# SilentStepStick-TMC2100_v13_5V.net
KiCad netlist of a schematic drawn in EAGLE
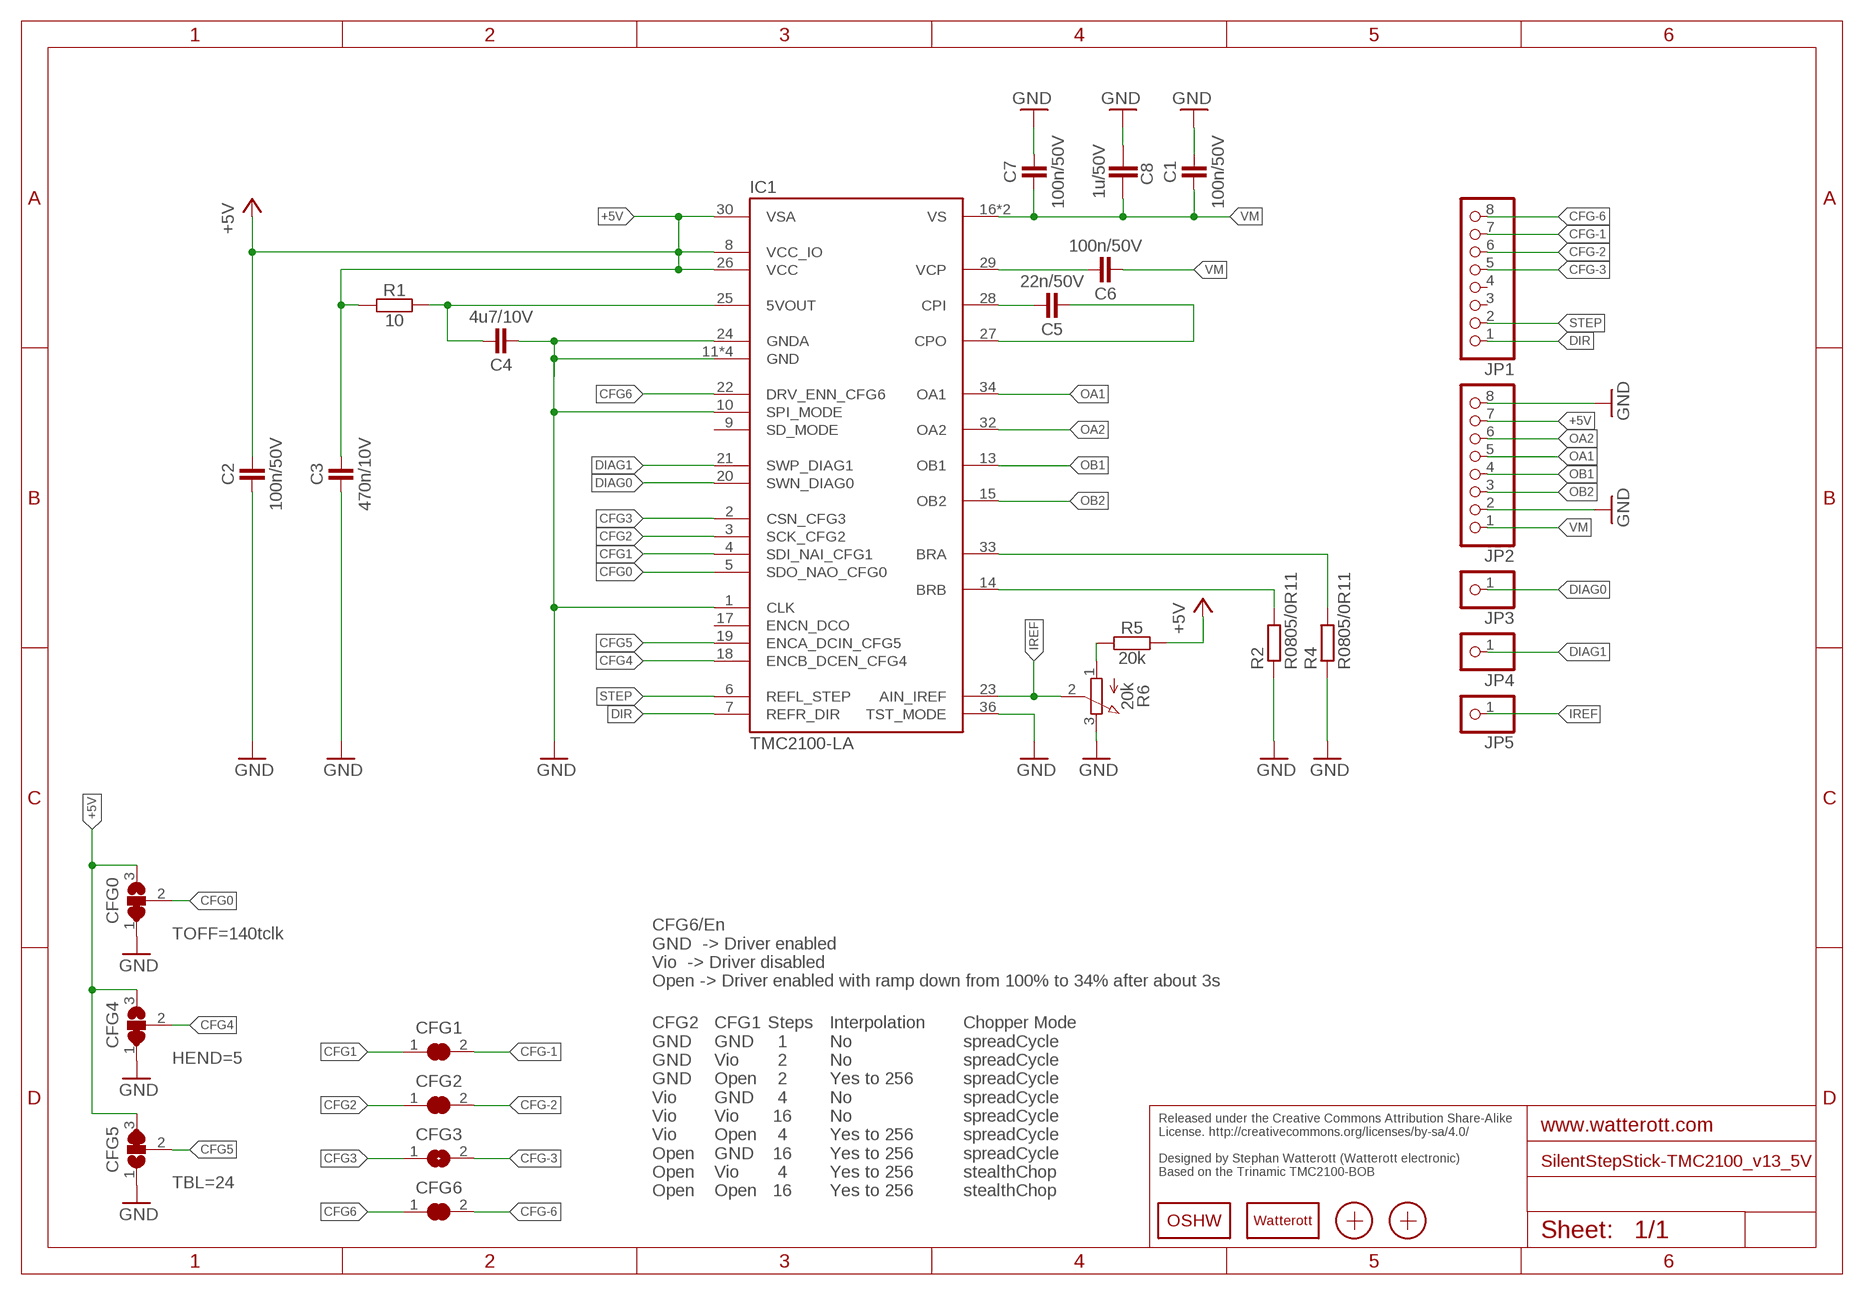
[diagram p0: schematic, sheet 1]

(export (version "E")
  (design (tool "Eeschema 10.0.6"))
  (components
    (comp (ref "C1")
      (value "100n/50V")
      (footprint "eagle-import:C0402")
      (libsource (lib "eagle-import") (part "CAPACITOR-0402"))
    )
    (comp (ref "C2")
      (value "100n/50V")
      (footprint "eagle-import:C0402")
      (libsource (lib "eagle-import") (part "CAPACITOR-0402"))
    )
    (comp (ref "C3")
      (value "470n/10V")
      (footprint "eagle-import:C0402")
      (libsource (lib "eagle-import") (part "CAPACITOR-0402"))
    )
    (comp (ref "C4")
      (value "4u7/10V")
      (footprint "eagle-import:C0402")
      (libsource (lib "eagle-import") (part "CAPACITOR-0402"))
    )
    (comp (ref "C5")
      (value "22n/50V")
      (footprint "eagle-import:C0402")
      (libsource (lib "eagle-import") (part "CAPACITOR-0402"))
    )
    (comp (ref "C6")
      (value "100n/50V")
      (footprint "eagle-import:C0402")
      (libsource (lib "eagle-import") (part "CAPACITOR-0402"))
    )
    (comp (ref "C7")
      (value "100n/50V")
      (footprint "eagle-import:C0402")
      (libsource (lib "eagle-import") (part "CAPACITOR-0402"))
    )
    (comp (ref "C8")
      (value "1u/50V")
      (footprint "eagle-import:C0603")
      (libsource (lib "eagle-import") (part "C-EUC0603"))
    )
    (comp (ref "CFG0")
      (value "JUMPER3-0201")
      (footprint "eagle-import:JUMPER3-0201")
      (libsource (lib "eagle-import") (part "JUMPER3-0201"))
    )
    (comp (ref "CFG1")
      (value "JUMPER2-0201")
      (footprint "eagle-import:JUMPER2-0201")
      (libsource (lib "eagle-import") (part "JUMPER2-0201"))
    )
    (comp (ref "CFG2")
      (value "JUMPER2-0201")
      (footprint "eagle-import:JUMPER2-0201")
      (libsource (lib "eagle-import") (part "JUMPER2-0201"))
    )
    (comp (ref "CFG3")
      (value "JUMPER2-0201")
      (footprint "eagle-import:JUMPER2-0201")
      (libsource (lib "eagle-import") (part "JUMPER2-0201"))
    )
    (comp (ref "CFG4")
      (value "JUMPER3-0201")
      (footprint "eagle-import:JUMPER3-0201")
      (libsource (lib "eagle-import") (part "JUMPER3-0201"))
    )
    (comp (ref "CFG5")
      (value "JUMPER3-0201")
      (footprint "eagle-import:JUMPER3-0201")
      (libsource (lib "eagle-import") (part "JUMPER3-0201"))
    )
    (comp (ref "CFG6")
      (value "JUMPER2-0201")
      (footprint "eagle-import:JUMPER2-0201")
      (libsource (lib "eagle-import") (part "JUMPER2-0201"))
    )
    (comp (ref "IC1")
      (value "TMC2100-LA")
      (footprint "eagle-import:QFN36-PAD")
      (libsource (lib "eagle-import") (part "TMC21X0-LA"))
    )
    (comp (ref "JP1")
      (value "PINHD-1X08_2.54-S")
      (footprint "eagle-import:1X08-S")
      (libsource (lib "eagle-import") (part "PINHD-1X08_2.54-S"))
    )
    (comp (ref "JP2")
      (value "PINHD-1X08_2.54-S")
      (footprint "eagle-import:1X08-S")
      (libsource (lib "eagle-import") (part "PINHD-1X08_2.54-S"))
    )
    (comp (ref "JP3")
      (value "PINHD-1X1")
      (footprint "eagle-import:1X01")
      (libsource (lib "eagle-import") (part "PINHD-1X1"))
    )
    (comp (ref "JP4")
      (value "PINHD-1X1")
      (footprint "eagle-import:1X01")
      (libsource (lib "eagle-import") (part "PINHD-1X1"))
    )
    (comp (ref "JP5")
      (value "PINHD-1X1")
      (footprint "eagle-import:1X01")
      (libsource (lib "eagle-import") (part "PINHD-1X1"))
    )
    (comp (ref "LOGO1")
      (value "OSHW_LOGOX0070")
      (footprint "eagle-import:OSHW_6X70")
      (libsource (lib "eagle-import") (part "OSHW_LOGOX0070"))
    )
    (comp (ref "LOGO2")
      (value "LOGO-S_PLACE_M")
      (footprint "eagle-import:SPARK_TPLACE_M")
      (libsource (lib "eagle-import") (part "LOGO-S_PLACE_M"))
    )
    (comp (ref "R1")
      (value "10")
      (footprint "eagle-import:C0402")
      (libsource (lib "eagle-import") (part "RESISTOR-0402"))
    )
    (comp (ref "R2")
      (value "R0805/0R11")
      (footprint "eagle-import:M0805")
      (libsource (lib "eagle-import") (part "R-EU_M0805"))
    )
    (comp (ref "R4")
      (value "R0805/0R11")
      (footprint "eagle-import:M0805")
      (libsource (lib "eagle-import") (part "R-EU_M0805"))
    )
    (comp (ref "R5")
      (value "20k")
      (footprint "eagle-import:C0402")
      (libsource (lib "eagle-import") (part "RESISTOR-0402"))
    )
    (comp (ref "R6")
      (value "20k")
      (footprint "eagle-import:POT_EVM3R")
      (libsource (lib "eagle-import") (part "POT-EVM3R"))
    )
    (comp (ref "X1")
      (value "PASSER-07")
      (footprint "eagle-import:PASSER_07MM")
      (libsource (lib "eagle-import") (part "PASSER-07"))
    )
    (comp (ref "X2")
      (value "PASSER-07")
      (footprint "eagle-import:PASSER_07MM")
      (libsource (lib "eagle-import") (part "PASSER-07"))
    )
  )
  (nets
    (net (code "1") (name "+5V") (class "Default")
      (node (ref "C2") (pin "2") (pinfunction "2_2") (pintype "passive"))
      (node (ref "C3") (pin "2") (pinfunction "2_2") (pintype "passive"))
      (node (ref "CFG0") (pin "3") (pinfunction "3_3") (pintype "passive"))
      (node (ref "CFG4") (pin "3") (pinfunction "3_3") (pintype "passive"))
      (node (ref "CFG5") (pin "3") (pinfunction "3_3") (pintype "passive"))
      (node (ref "IC1") (pin "26") (pinfunction "VCC_26") (pintype "power_in"))
      (node (ref "IC1") (pin "30") (pinfunction "VSA_30") (pintype "power_in"))
      (node (ref "IC1") (pin "8") (pinfunction "VCC_IO_8") (pintype "power_in"))
      (node (ref "JP2") (pin "7") (pinfunction "7_7") (pintype "passive"))
      (node (ref "R1") (pin "1") (pinfunction "1_1") (pintype "passive"))
      (node (ref "R5") (pin "2") (pinfunction "2_2") (pintype "passive"))
    )
    (net (code "2") (name "CFG-1") (class "Default")
      (node (ref "CFG1") (pin "2") (pinfunction "2_2") (pintype "passive"))
      (node (ref "JP1") (pin "7") (pinfunction "7_7") (pintype "passive"))
    )
    (net (code "3") (name "CFG-2") (class "Default")
      (node (ref "CFG2") (pin "2") (pinfunction "2_2") (pintype "passive"))
      (node (ref "JP1") (pin "6") (pinfunction "6_6") (pintype "passive"))
    )
    (net (code "4") (name "CFG-3") (class "Default")
      (node (ref "CFG3") (pin "2") (pinfunction "2_2") (pintype "passive"))
      (node (ref "JP1") (pin "5") (pinfunction "5_5") (pintype "passive"))
    )
    (net (code "5") (name "CFG-6") (class "Default")
      (node (ref "CFG6") (pin "2") (pinfunction "2_2") (pintype "passive"))
      (node (ref "JP1") (pin "8") (pinfunction "8_8") (pintype "passive"))
    )
    (net (code "6") (name "CFG0") (class "Default")
      (node (ref "CFG0") (pin "2") (pinfunction "2_2") (pintype "passive"))
      (node (ref "IC1") (pin "5") (pinfunction "SDO_NAO_CFG0_5") (pintype "bidirectional"))
    )
    (net (code "7") (name "CFG1") (class "Default")
      (node (ref "CFG1") (pin "1") (pinfunction "1_1") (pintype "passive"))
      (node (ref "IC1") (pin "4") (pinfunction "SDI_NAI_CFG1_4") (pintype "bidirectional"))
    )
    (net (code "8") (name "CFG2") (class "Default")
      (node (ref "CFG2") (pin "1") (pinfunction "1_1") (pintype "passive"))
      (node (ref "IC1") (pin "3") (pinfunction "SCK_CFG2_3") (pintype "bidirectional"))
    )
    (net (code "9") (name "CFG3") (class "Default")
      (node (ref "CFG3") (pin "1") (pinfunction "1_1") (pintype "passive"))
      (node (ref "IC1") (pin "2") (pinfunction "CSN_CFG3_2") (pintype "bidirectional"))
    )
    (net (code "10") (name "CFG4") (class "Default")
      (node (ref "CFG4") (pin "2") (pinfunction "2_2") (pintype "passive"))
      (node (ref "IC1") (pin "18") (pinfunction "ENCB_DCEN_CFG4_18") (pintype "bidirectional"))
    )
    (net (code "11") (name "CFG5") (class "Default")
      (node (ref "CFG5") (pin "2") (pinfunction "2_2") (pintype "passive"))
      (node (ref "IC1") (pin "19") (pinfunction "ENCA_DCIN_CFG5_19") (pintype "bidirectional"))
    )
    (net (code "12") (name "CFG6") (class "Default")
      (node (ref "CFG6") (pin "1") (pinfunction "1_1") (pintype "passive"))
      (node (ref "IC1") (pin "22") (pinfunction "DRV_ENN_CFG6_22") (pintype "bidirectional"))
    )
    (net (code "13") (name "DIAG0") (class "Default")
      (node (ref "IC1") (pin "20") (pinfunction "SWN_DIAG0_20") (pintype "bidirectional"))
      (node (ref "JP3") (pin "1") (pinfunction "1_1") (pintype "passive"))
    )
    (net (code "14") (name "DIAG1") (class "Default")
      (node (ref "IC1") (pin "21") (pinfunction "SWP_DIAG1_21") (pintype "bidirectional"))
      (node (ref "JP4") (pin "1") (pinfunction "1_1") (pintype "passive"))
    )
    (net (code "15") (name "DIR") (class "Default")
      (node (ref "IC1") (pin "7") (pinfunction "REFR_DIR_7") (pintype "bidirectional"))
      (node (ref "JP1") (pin "1") (pinfunction "1_1") (pintype "passive"))
    )
    (net (code "16") (name "GND") (class "Default")
      (node (ref "C1") (pin "2") (pinfunction "2_2") (pintype "passive"))
      (node (ref "C2") (pin "1") (pinfunction "1_1") (pintype "passive"))
      (node (ref "C3") (pin "1") (pinfunction "1_1") (pintype "passive"))
      (node (ref "C4") (pin "1") (pinfunction "1_1") (pintype "passive"))
      (node (ref "C7") (pin "2") (pinfunction "2_2") (pintype "passive"))
      (node (ref "C8") (pin "2") (pinfunction "2_2") (pintype "passive"))
      (node (ref "CFG0") (pin "1") (pinfunction "1_1") (pintype "passive"))
      (node (ref "CFG4") (pin "1") (pinfunction "1_1") (pintype "passive"))
      (node (ref "CFG5") (pin "1") (pinfunction "1_1") (pintype "passive"))
      (node (ref "IC1") (pin "1") (pinfunction "CLK_1") (pintype "bidirectional"))
      (node (ref "IC1") (pin "10") (pinfunction "SPI_MODE_10") (pintype "bidirectional"))
      (node (ref "IC1") (pin "11") (pinfunction "GND_11") (pintype "power_in"))
      (node (ref "IC1") (pin "12") (pinfunction "GND_12") (pintype "power_in"))
      (node (ref "IC1") (pin "24") (pinfunction "GNDA_24") (pintype "power_in"))
      (node (ref "IC1") (pin "35") (pinfunction "GND_35") (pintype "power_in"))
      (node (ref "IC1") (pin "36") (pinfunction "TST_MODE_36") (pintype "bidirectional"))
      (node (ref "IC1") (pin "TP") (pinfunction "GND_TP") (pintype "power_in"))
      (node (ref "JP2") (pin "2") (pinfunction "2_2") (pintype "passive"))
      (node (ref "JP2") (pin "8") (pinfunction "8_8") (pintype "passive"))
      (node (ref "R2") (pin "1") (pinfunction "1_1") (pintype "passive"))
      (node (ref "R4") (pin "1") (pinfunction "1_1") (pintype "passive"))
      (node (ref "R6") (pin "3") (pinfunction "E_3") (pintype "passive"))
    )
    (net (code "17") (name "IREF") (class "Default")
      (node (ref "IC1") (pin "23") (pinfunction "AIN_IREF_23") (pintype "passive"))
      (node (ref "JP5") (pin "1") (pinfunction "1_1") (pintype "passive"))
      (node (ref "R6") (pin "2") (pinfunction "S_2") (pintype "passive"))
    )
    (net (code "18") (name "Net-(IC1-5VOUT)") (class "Default")
      (node (ref "C4") (pin "2") (pinfunction "2_2") (pintype "passive"))
      (node (ref "IC1") (pin "25") (pinfunction "5VOUT_25") (pintype "power_in"))
      (node (ref "R1") (pin "2") (pinfunction "2_2") (pintype "passive"))
    )
    (net (code "19") (name "Net-(IC1-BRA)") (class "Default")
      (node (ref "IC1") (pin "33") (pinfunction "BRA_33") (pintype "output"))
      (node (ref "R4") (pin "2") (pinfunction "2_2") (pintype "passive"))
    )
    (net (code "20") (name "Net-(IC1-BRB)") (class "Default")
      (node (ref "IC1") (pin "14") (pinfunction "BRB_14") (pintype "output"))
      (node (ref "R2") (pin "2") (pinfunction "2_2") (pintype "passive"))
    )
    (net (code "21") (name "Net-(IC1-CPI)") (class "Default")
      (node (ref "C5") (pin "2") (pinfunction "2_2") (pintype "passive"))
      (node (ref "IC1") (pin "28") (pinfunction "CPI_28") (pintype "passive"))
    )
    (net (code "22") (name "Net-(IC1-CPO)") (class "Default")
      (node (ref "C5") (pin "1") (pinfunction "1_1") (pintype "passive"))
      (node (ref "IC1") (pin "27") (pinfunction "CPO_27") (pintype "passive"))
    )
    (net (code "23") (name "Net-(IC1-VCP)") (class "Default")
      (node (ref "C6") (pin "2") (pinfunction "2_2") (pintype "passive"))
      (node (ref "IC1") (pin "29") (pinfunction "VCP_29") (pintype "passive"))
    )
    (net (code "24") (name "Net-(R6-A)") (class "Default")
      (node (ref "R5") (pin "1") (pinfunction "1_1") (pintype "passive"))
      (node (ref "R6") (pin "1") (pinfunction "A_1") (pintype "passive"))
    )
    (net (code "25") (name "OA1") (class "Default")
      (node (ref "IC1") (pin "34") (pinfunction "OA1_34") (pintype "output"))
      (node (ref "JP2") (pin "5") (pinfunction "5_5") (pintype "passive"))
    )
    (net (code "26") (name "OA2") (class "Default")
      (node (ref "IC1") (pin "32") (pinfunction "OA2_32") (pintype "output"))
      (node (ref "JP2") (pin "6") (pinfunction "6_6") (pintype "passive"))
    )
    (net (code "27") (name "OB1") (class "Default")
      (node (ref "IC1") (pin "13") (pinfunction "OB1_13") (pintype "output"))
      (node (ref "JP2") (pin "4") (pinfunction "4_4") (pintype "passive"))
    )
    (net (code "28") (name "OB2") (class "Default")
      (node (ref "IC1") (pin "15") (pinfunction "OB2_15") (pintype "output"))
      (node (ref "JP2") (pin "3") (pinfunction "3_3") (pintype "passive"))
    )
    (net (code "29") (name "STEP") (class "Default")
      (node (ref "IC1") (pin "6") (pinfunction "REFL_STEP_6") (pintype "bidirectional"))
      (node (ref "JP1") (pin "2") (pinfunction "2_2") (pintype "passive"))
    )
    (net (code "30") (name "VM") (class "Default")
      (node (ref "C1") (pin "1") (pinfunction "1_1") (pintype "passive"))
      (node (ref "C6") (pin "1") (pinfunction "1_1") (pintype "passive"))
      (node (ref "C7") (pin "1") (pinfunction "1_1") (pintype "passive"))
      (node (ref "C8") (pin "1") (pinfunction "1_1") (pintype "passive"))
      (node (ref "IC1") (pin "16") (pinfunction "VS_16") (pintype "power_in"))
      (node (ref "IC1") (pin "31") (pinfunction "VS_31") (pintype "power_in"))
      (node (ref "JP2") (pin "1") (pinfunction "1_1") (pintype "passive"))
    )
    (net (code "31") (name "unconnected-(IC1-ENCN_DCO-Pad17)") (class "Default")
      (node (ref "IC1") (pin "17") (pinfunction "ENCN_DCO_17") (pintype "bidirectional"))
    )
    (net (code "32") (name "unconnected-(IC1-SD_MODE-Pad9)") (class "Default")
      (node (ref "IC1") (pin "9") (pinfunction "SD_MODE_9") (pintype "bidirectional"))
    )
    (net (code "33") (name "unconnected-(JP1-Pad3)") (class "Default")
      (node (ref "JP1") (pin "3") (pinfunction "3_3") (pintype "passive"))
    )
    (net (code "34") (name "unconnected-(JP1-Pad4)") (class "Default")
      (node (ref "JP1") (pin "4") (pinfunction "4_4") (pintype "passive"))
    )
  )
)
